# PIR_Sensor_Card.net
KiCad netlist of a schematic drawn in EAGLE
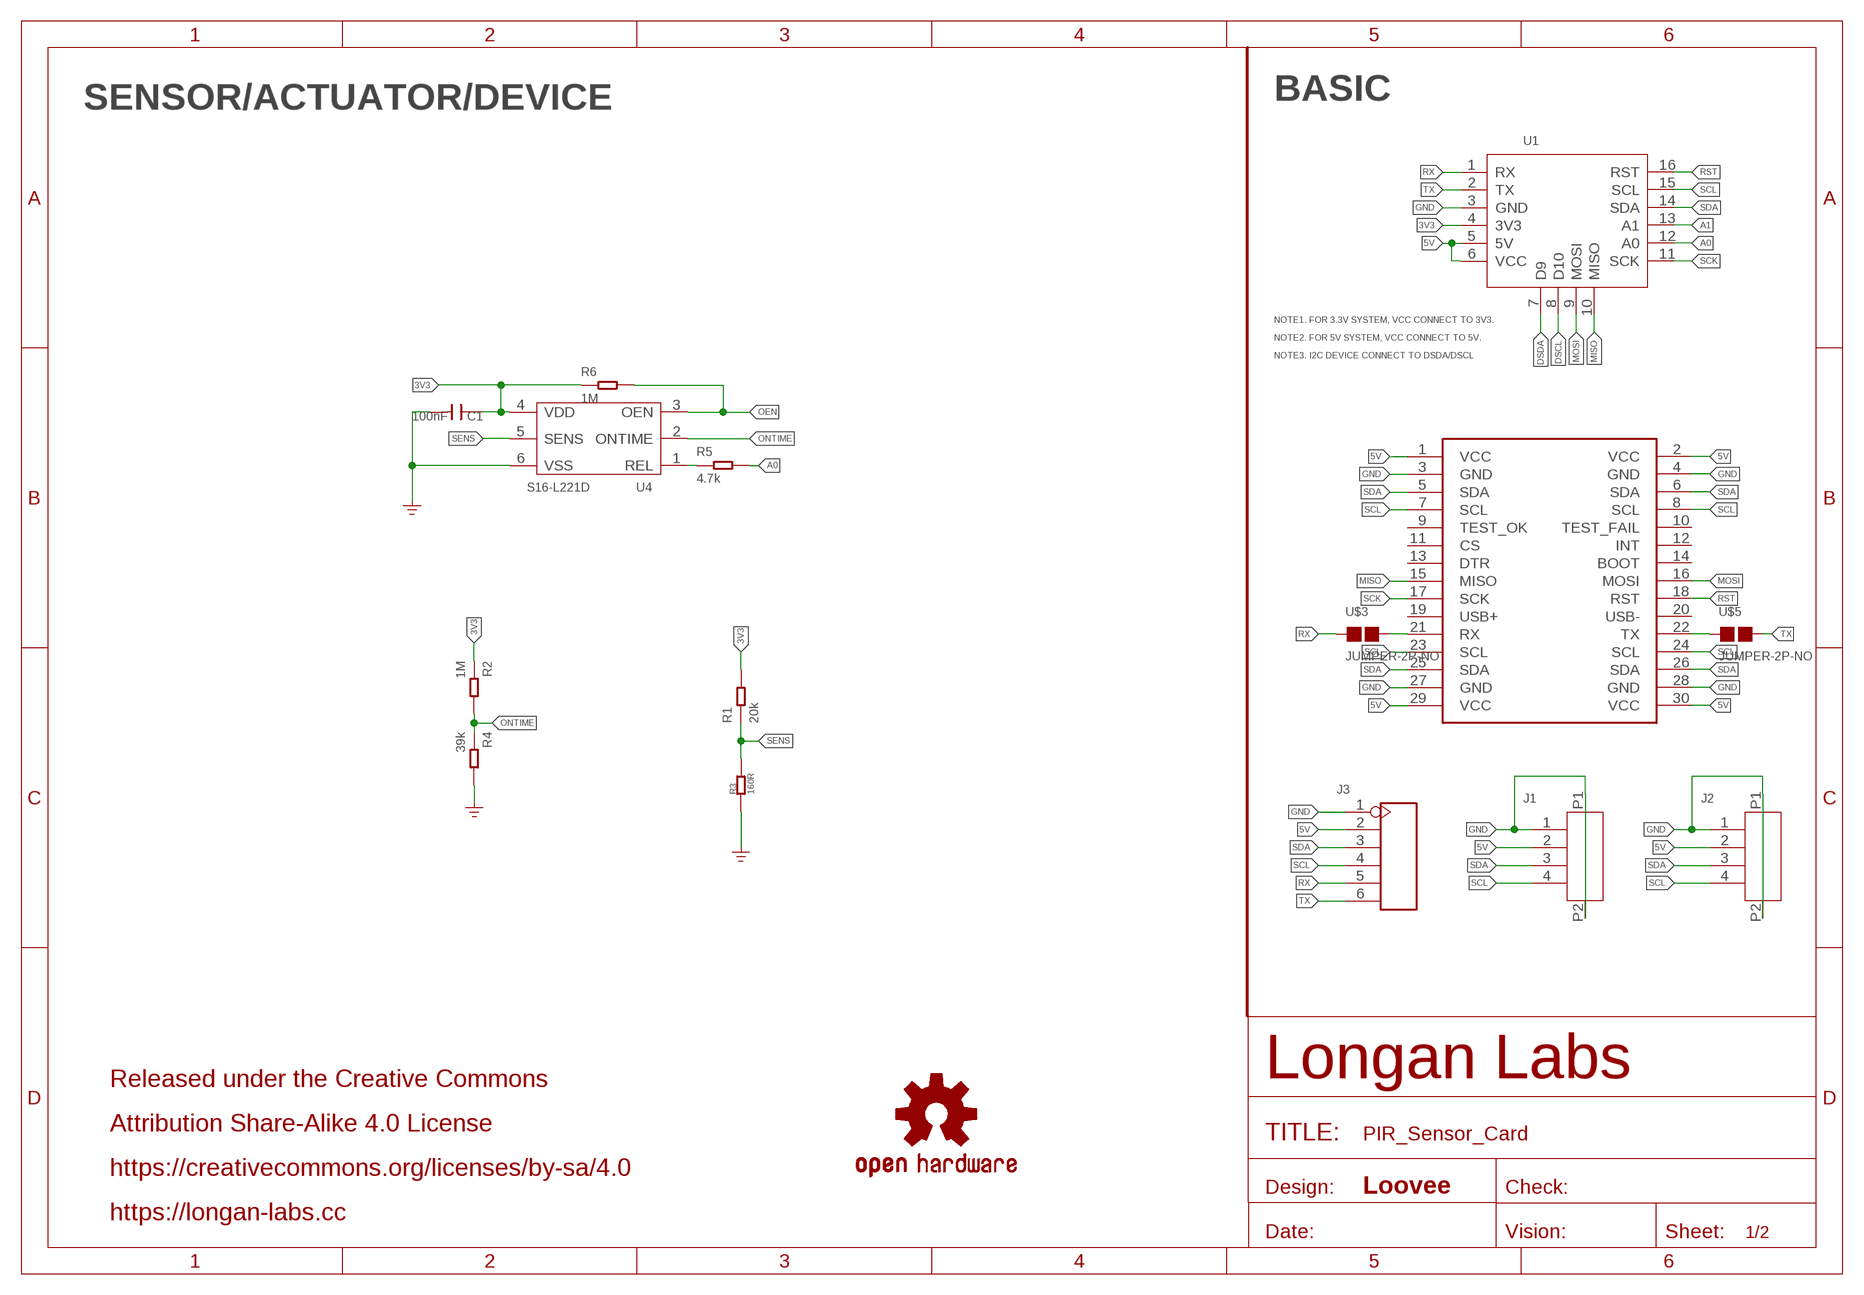
[diagram p0: schematic, sheet 1]

(export (version "E")
  (design (tool "Eeschema 10.0.6"))
  (components
    (comp (ref "C1")
      (value "100nF")
      (footprint "eagle-import:C0603")
      (libsource (lib "eagle-import") (part "CAP-0603"))
    )
    (comp (ref "J1")
      (value "HEADER-4P-1.0")
      (footprint "eagle-import:4P-1.0-90D")
      (libsource (lib "eagle-import") (part "HEADER-4P-1.0"))
    )
    (comp (ref "J2")
      (value "HEADER-4P-1.0")
      (footprint "eagle-import:4P-1.0-90D")
      (libsource (lib "eagle-import") (part "HEADER-4P-1.0"))
    )
    (comp (ref "J3")
      (value "HEADER-6P-55/35MIL")
      (footprint "eagle-import:H6-2.54")
      (libsource (lib "eagle-import") (part "HEADER-6P-55/35MIL"))
    )
    (comp (ref "LOGO2")
      (value "OSHW-LOGOS")
      (footprint "eagle-import:OSHW-LOGO-S")
      (libsource (lib "eagle-import") (part "OSHW-LOGOS"))
    )
    (comp (ref "MOUDLE1")
      (value "MOUDLE-2X15P-2.54'BOARD'")
      (footprint "eagle-import:MOUDLE-2X15P-2.54")
      (libsource (lib "eagle-import") (part "MOUDLE-2X15P-2.54'BOARD'"))
    )
    (comp (ref "R1")
      (value "20k")
      (footprint "eagle-import:R0603")
      (libsource (lib "eagle-import") (part "RES-0603"))
    )
    (comp (ref "R2")
      (value "1M")
      (footprint "eagle-import:R0603")
      (libsource (lib "eagle-import") (part "RES-0603"))
    )
    (comp (ref "R3")
      (value "160R")
      (footprint "eagle-import:R0603")
      (libsource (lib "eagle-import") (part "RES-0603"))
    )
    (comp (ref "R4")
      (value "39k")
      (footprint "eagle-import:R0603")
      (libsource (lib "eagle-import") (part "RES-0603"))
    )
    (comp (ref "R5")
      (value "4.7k")
      (footprint "eagle-import:R0603")
      (libsource (lib "eagle-import") (part "RES-0603"))
    )
    (comp (ref "R6")
      (value "1M")
      (footprint "eagle-import:R0603")
      (libsource (lib "eagle-import") (part "RES-0603"))
    )
    (comp (ref "U$3")
      (value "JUMPER-2P-NO")
      (footprint "eagle-import:2P-SMD-NO")
      (libsource (lib "eagle-import") (part "JUMPER-2P-NO"))
    )
    (comp (ref "U$5")
      (value "JUMPER-2P-NO")
      (footprint "eagle-import:2P-SMD-NO")
      (libsource (lib "eagle-import") (part "JUMPER-2P-NO"))
    )
    (comp (ref "U1")
      (value "MOUDLE-CARDS")
      (footprint "eagle-import:16P-2.0-CARDS")
      (libsource (lib "eagle-import") (part "MOUDLE-CARDS"))
    )
    (comp (ref "U4")
      (value "S16-L221D")
      (footprint "eagle-import:6P-SMD-6X6MM")
      (libsource (lib "eagle-import") (part "S16-L221D"))
    )
  )
  (nets
    (net (code "1") (name "3V3") (class "Default")
      (node (ref "C1") (pin "1") (pinfunction "1_1") (pintype "passive"))
      (node (ref "R1") (pin "2") (pinfunction "2_2") (pintype "passive"))
      (node (ref "R2") (pin "1") (pinfunction "1_1") (pintype "passive"))
      (node (ref "R6") (pin "1") (pinfunction "1_1") (pintype "passive"))
      (node (ref "U1") (pin "4") (pinfunction "3V3_4") (pintype "bidirectional"))
      (node (ref "U4") (pin "4") (pinfunction "VDD_4") (pintype "bidirectional"))
    )
    (net (code "2") (name "5V") (class "Default")
      (node (ref "J1") (pin "2") (pinfunction "2_2") (pintype "bidirectional"))
      (node (ref "J2") (pin "2") (pinfunction "2_2") (pintype "bidirectional"))
      (node (ref "J3") (pin "2") (pinfunction "2_2") (pintype "bidirectional"))
      (node (ref "MOUDLE1") (pin "1") (pinfunction "VCC_1") (pintype "bidirectional"))
      (node (ref "MOUDLE1") (pin "2") (pinfunction "VCC_2") (pintype "bidirectional"))
      (node (ref "MOUDLE1") (pin "29") (pinfunction "VCC_29") (pintype "bidirectional"))
      (node (ref "MOUDLE1") (pin "30") (pinfunction "VCC_30") (pintype "bidirectional"))
      (node (ref "U1") (pin "5") (pinfunction "5V_5") (pintype "bidirectional"))
      (node (ref "U1") (pin "6") (pinfunction "VCC_6") (pintype "bidirectional"))
    )
    (net (code "3") (name "A0") (class "Default")
      (node (ref "R5") (pin "2") (pinfunction "2_2") (pintype "passive"))
      (node (ref "U1") (pin "12") (pinfunction "A0_12") (pintype "bidirectional"))
    )
    (net (code "4") (name "A1") (class "Default")
      (node (ref "U1") (pin "13") (pinfunction "A1_13") (pintype "bidirectional"))
    )
    (net (code "5") (name "DSCL") (class "Default")
      (node (ref "U1") (pin "8") (pinfunction "D10_8") (pintype "bidirectional"))
    )
    (net (code "6") (name "DSDA") (class "Default")
      (node (ref "U1") (pin "7") (pinfunction "D9_7") (pintype "bidirectional"))
    )
    (net (code "7") (name "GND") (class "Default")
      (node (ref "C1") (pin "2") (pinfunction "2_2") (pintype "passive"))
      (node (ref "J1") (pin "1") (pinfunction "1_1") (pintype "bidirectional"))
      (node (ref "J1") (pin "P1") (pinfunction "P1_P1") (pintype "bidirectional"))
      (node (ref "J1") (pin "P2") (pinfunction "P2_P2") (pintype "bidirectional"))
      (node (ref "J2") (pin "1") (pinfunction "1_1") (pintype "bidirectional"))
      (node (ref "J2") (pin "P1") (pinfunction "P1_P1") (pintype "bidirectional"))
      (node (ref "J2") (pin "P2") (pinfunction "P2_P2") (pintype "bidirectional"))
      (node (ref "J3") (pin "1") (pinfunction "1_1") (pintype "bidirectional"))
      (node (ref "MOUDLE1") (pin "27") (pinfunction "GND_27") (pintype "bidirectional"))
      (node (ref "MOUDLE1") (pin "28") (pinfunction "GND_28") (pintype "bidirectional"))
      (node (ref "MOUDLE1") (pin "3") (pinfunction "GND_3") (pintype "bidirectional"))
      (node (ref "MOUDLE1") (pin "4") (pinfunction "GND_4") (pintype "bidirectional"))
      (node (ref "R3") (pin "1") (pinfunction "1_1") (pintype "passive"))
      (node (ref "R4") (pin "2") (pinfunction "2_2") (pintype "passive"))
      (node (ref "U1") (pin "3") (pinfunction "GND_3") (pintype "bidirectional"))
      (node (ref "U4") (pin "6") (pinfunction "VSS_6") (pintype "bidirectional"))
    )
    (net (code "8") (name "MISO") (class "Default")
      (node (ref "MOUDLE1") (pin "15") (pinfunction "MISO_15") (pintype "bidirectional"))
      (node (ref "U1") (pin "10") (pinfunction "MISO_10") (pintype "bidirectional"))
    )
    (net (code "9") (name "MOSI") (class "Default")
      (node (ref "MOUDLE1") (pin "16") (pinfunction "MOSI_16") (pintype "bidirectional"))
      (node (ref "U1") (pin "9") (pinfunction "MOSI_9") (pintype "bidirectional"))
    )
    (net (code "10") (name "Net-(MOUDLE1-RX)") (class "Default")
      (node (ref "MOUDLE1") (pin "21") (pinfunction "RX_21") (pintype "bidirectional"))
      (node (ref "U$3") (pin "2") (pinfunction "2_2") (pintype "bidirectional"))
    )
    (net (code "11") (name "Net-(MOUDLE1-TX)") (class "Default")
      (node (ref "MOUDLE1") (pin "22") (pinfunction "TX_22") (pintype "bidirectional"))
      (node (ref "U$5") (pin "1") (pinfunction "1_1") (pintype "bidirectional"))
    )
    (net (code "12") (name "Net-(U4-REL)") (class "Default")
      (node (ref "R5") (pin "1") (pinfunction "1_1") (pintype "passive"))
      (node (ref "U4") (pin "1") (pinfunction "REL_1") (pintype "bidirectional"))
    )
    (net (code "13") (name "OEN") (class "Default")
      (node (ref "R6") (pin "2") (pinfunction "2_2") (pintype "passive"))
      (node (ref "U4") (pin "3") (pinfunction "OEN_3") (pintype "bidirectional"))
    )
    (net (code "14") (name "ONTIME") (class "Default")
      (node (ref "R2") (pin "2") (pinfunction "2_2") (pintype "passive"))
      (node (ref "R4") (pin "1") (pinfunction "1_1") (pintype "passive"))
      (node (ref "U4") (pin "2") (pinfunction "ONTIME_2") (pintype "bidirectional"))
    )
    (net (code "15") (name "RST") (class "Default")
      (node (ref "MOUDLE1") (pin "18") (pinfunction "RST_18") (pintype "bidirectional"))
      (node (ref "U1") (pin "16") (pinfunction "RST_16") (pintype "bidirectional"))
    )
    (net (code "16") (name "RX") (class "Default")
      (node (ref "J3") (pin "5") (pinfunction "5_5") (pintype "bidirectional"))
      (node (ref "U$3") (pin "1") (pinfunction "1_1") (pintype "bidirectional"))
      (node (ref "U1") (pin "1") (pinfunction "RX_1") (pintype "bidirectional"))
    )
    (net (code "17") (name "SCK") (class "Default")
      (node (ref "MOUDLE1") (pin "17") (pinfunction "SCK_17") (pintype "bidirectional"))
      (node (ref "U1") (pin "11") (pinfunction "SCK_11") (pintype "bidirectional"))
    )
    (net (code "18") (name "SCL") (class "Default")
      (node (ref "J1") (pin "4") (pinfunction "4_4") (pintype "bidirectional"))
      (node (ref "J2") (pin "4") (pinfunction "4_4") (pintype "bidirectional"))
      (node (ref "J3") (pin "4") (pinfunction "4_4") (pintype "bidirectional"))
      (node (ref "MOUDLE1") (pin "23") (pinfunction "SCL_23") (pintype "bidirectional"))
      (node (ref "MOUDLE1") (pin "24") (pinfunction "SCL_24") (pintype "bidirectional"))
      (node (ref "MOUDLE1") (pin "7") (pinfunction "SCL_7") (pintype "bidirectional"))
      (node (ref "MOUDLE1") (pin "8") (pinfunction "SCL_8") (pintype "bidirectional"))
      (node (ref "U1") (pin "15") (pinfunction "SCL_15") (pintype "bidirectional"))
    )
    (net (code "19") (name "SDA") (class "Default")
      (node (ref "J1") (pin "3") (pinfunction "3_3") (pintype "bidirectional"))
      (node (ref "J2") (pin "3") (pinfunction "3_3") (pintype "bidirectional"))
      (node (ref "J3") (pin "3") (pinfunction "3_3") (pintype "bidirectional"))
      (node (ref "MOUDLE1") (pin "25") (pinfunction "SDA_25") (pintype "bidirectional"))
      (node (ref "MOUDLE1") (pin "26") (pinfunction "SDA_26") (pintype "bidirectional"))
      (node (ref "MOUDLE1") (pin "5") (pinfunction "SDA_5") (pintype "bidirectional"))
      (node (ref "MOUDLE1") (pin "6") (pinfunction "SDA_6") (pintype "bidirectional"))
      (node (ref "U1") (pin "14") (pinfunction "SDA_14") (pintype "bidirectional"))
    )
    (net (code "20") (name "SENS") (class "Default")
      (node (ref "R1") (pin "1") (pinfunction "1_1") (pintype "passive"))
      (node (ref "R3") (pin "2") (pinfunction "2_2") (pintype "passive"))
      (node (ref "U4") (pin "5") (pinfunction "SENS_5") (pintype "bidirectional"))
    )
    (net (code "21") (name "TX") (class "Default")
      (node (ref "J3") (pin "6") (pinfunction "6_6") (pintype "bidirectional"))
      (node (ref "U$5") (pin "2") (pinfunction "2_2") (pintype "bidirectional"))
      (node (ref "U1") (pin "2") (pinfunction "TX_2") (pintype "bidirectional"))
    )
    (net (code "22") (name "unconnected-(MOUDLE1-BOOT-Pad14)") (class "Default")
      (node (ref "MOUDLE1") (pin "14") (pinfunction "BOOT_14") (pintype "bidirectional"))
    )
    (net (code "23") (name "unconnected-(MOUDLE1-CS-Pad11)") (class "Default")
      (node (ref "MOUDLE1") (pin "11") (pinfunction "CS_11") (pintype "bidirectional"))
    )
    (net (code "24") (name "unconnected-(MOUDLE1-DTR-Pad13)") (class "Default")
      (node (ref "MOUDLE1") (pin "13") (pinfunction "DTR_13") (pintype "bidirectional"))
    )
    (net (code "25") (name "unconnected-(MOUDLE1-INT-Pad12)") (class "Default")
      (node (ref "MOUDLE1") (pin "12") (pinfunction "INT_12") (pintype "bidirectional"))
    )
    (net (code "26") (name "unconnected-(MOUDLE1-TEST_FAIL-Pad10)") (class "Default")
      (node (ref "MOUDLE1") (pin "10") (pinfunction "TEST_FAIL_10") (pintype "bidirectional"))
    )
    (net (code "27") (name "unconnected-(MOUDLE1-TEST_OK-Pad9)") (class "Default")
      (node (ref "MOUDLE1") (pin "9") (pinfunction "TEST_OK_9") (pintype "bidirectional"))
    )
    (net (code "28") (name "unconnected-(MOUDLE1-USB+-Pad19)") (class "Default")
      (node (ref "MOUDLE1") (pin "19") (pinfunction "USB+_19") (pintype "bidirectional"))
    )
    (net (code "29") (name "unconnected-(MOUDLE1-USB--Pad20)") (class "Default")
      (node (ref "MOUDLE1") (pin "20") (pinfunction "USB-_20") (pintype "bidirectional"))
    )
  )
)
